# SCH_Blinking-Maple-PCB_2025-10-30.net
KiCad netlist of a schematic drawn in EasyEDA
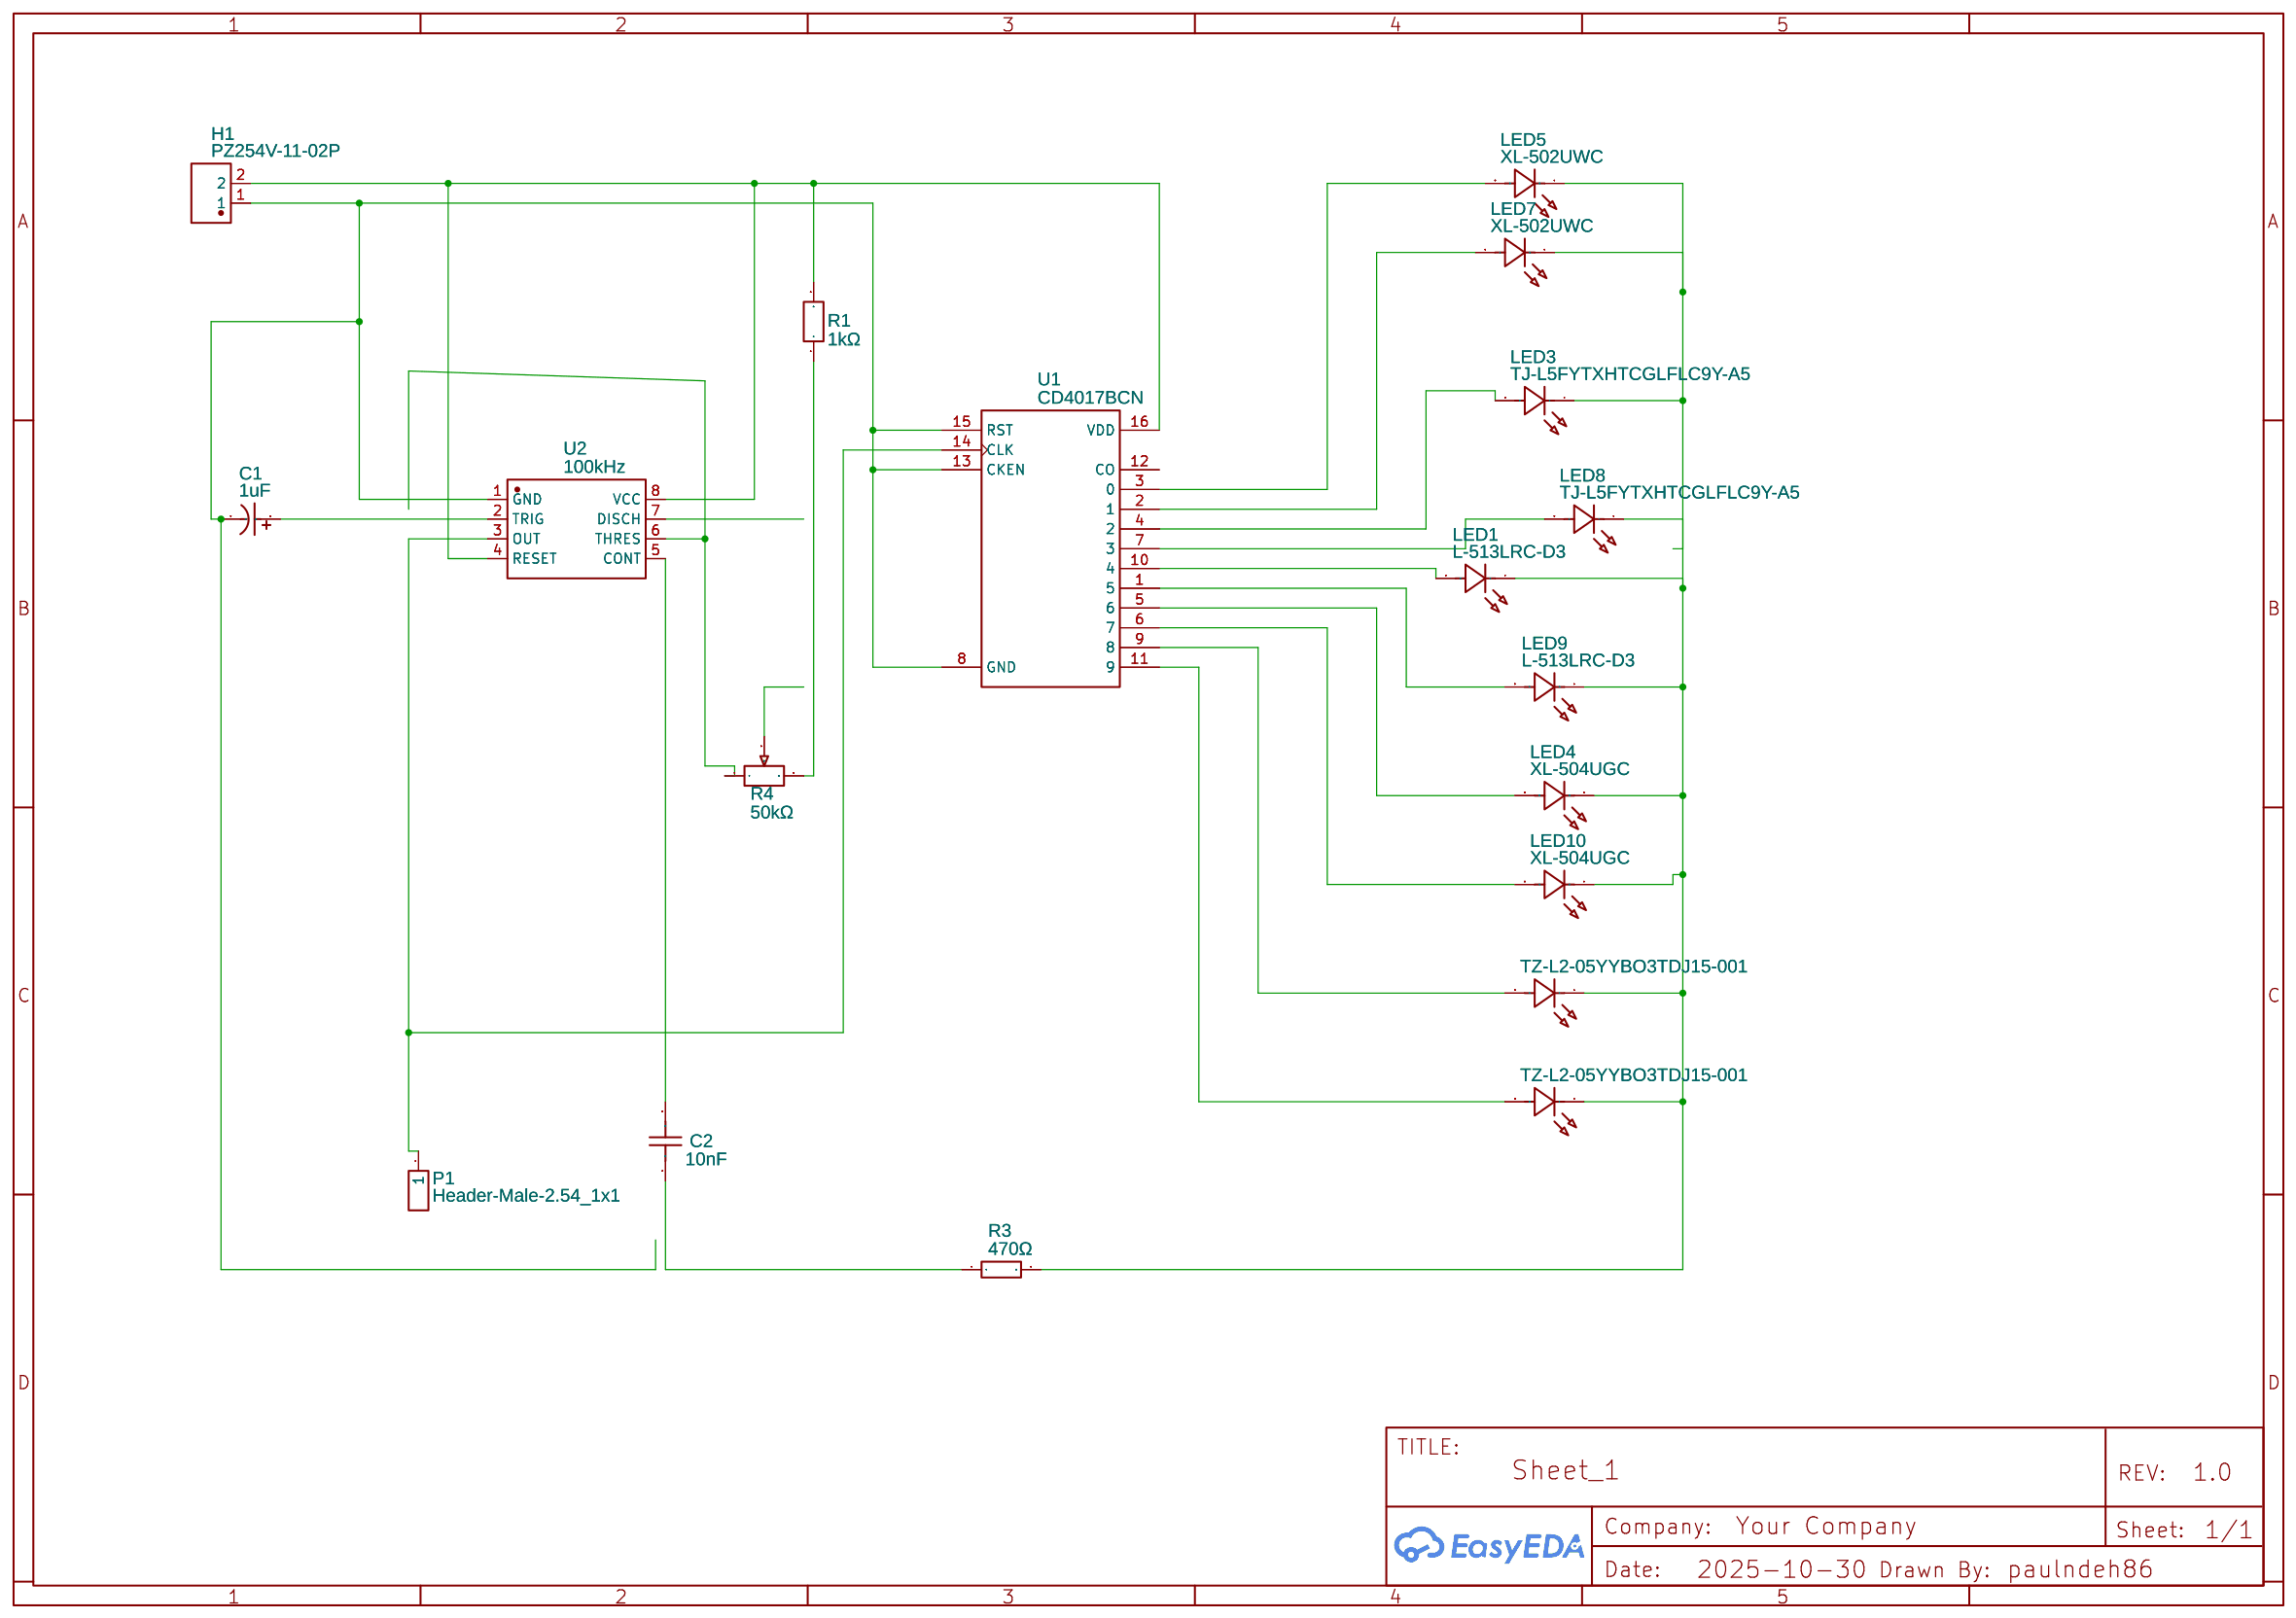
[diagram p0: schematic sheet]

(export (version "E")
  (design (tool "Eeschema 10.0.6"))
  (components
    (comp (ref "C1")
      (value "1uF")
      (fields (field (name "Manufacturer Part") "KF010M050C110A") (field (name "Manufacturer") "CapXon(丰宾)"))
      (libsource (lib "") (part "KF010M050C110A"))
    )
    (comp (ref "C2")
      (value "10nF")
      (fields (field (name "Manufacturer Part") "N09F1B103MN0B0S0N0") (field (name "Manufacturer") "STE(松田)"))
      (libsource (lib "") (part "N09F1B103MN0B0S0N0"))
    )
    (comp (ref "H1")
      (value "PZ254V-11-02P")
      (fields (field (name "Manufacturer") "XFCN(兴飞)"))
      (libsource (lib "") (part "PZ254V-11-02P"))
    )
    (comp (ref "LED1")
      (value "L-513LRC-D3")
      (fields (field (name "Manufacturer") "PARALIGHT(光鼎)"))
      (libsource (lib "") (part "L-513LRC-D3"))
    )
    (comp (ref "LED2")
      (value "TZ-L2-05YYBO3TDJ15-001")
      (fields (field (name "Manufacturer") "TUOZHAN(拓展光电)"))
      (libsource (lib "") (part "TZ-L2-05YYBO3TDJ15-001"))
    )
    (comp (ref "LED3")
      (value "TJ-L5FYTXHTCGLFLC9Y-A5")
      (fields (field (name "Manufacturer") "TOGIALED(统佳)"))
      (libsource (lib "") (part "TJ-L5FYTXHTCGLFLC9Y-A5"))
    )
    (comp (ref "LED4")
      (value "XL-504UGC")
      (fields (field (name "Manufacturer") "XINGLIGHT(成兴光)"))
      (libsource (lib "") (part "XL-504UGC"))
    )
    (comp (ref "LED5")
      (value "XL-502UWC")
      (fields (field (name "Manufacturer") "XINGLIGHT(成兴光)"))
      (libsource (lib "") (part "XL-502UWC"))
    )
    (comp (ref "LED7")
      (value "XL-502UWC")
      (fields (field (name "Manufacturer") "XINGLIGHT(成兴光)"))
      (libsource (lib "") (part "XL-502UWC"))
    )
    (comp (ref "LED8")
      (value "TJ-L5FYTXHTCGLFLC9Y-A5")
      (fields (field (name "Manufacturer") "TOGIALED(统佳)"))
      (libsource (lib "") (part "TJ-L5FYTXHTCGLFLC9Y-A5"))
    )
    (comp (ref "LED9")
      (value "L-513LRC-D3")
      (fields (field (name "Manufacturer") "PARALIGHT(光鼎)"))
      (libsource (lib "") (part "L-513LRC-D3"))
    )
    (comp (ref "LED10")
      (value "XL-504UGC")
      (fields (field (name "Manufacturer") "XINGLIGHT(成兴光)"))
      (libsource (lib "") (part "XL-504UGC"))
    )
    (comp (ref "LED11")
      (value "TZ-L2-05YYBO3TDJ15-001")
      (fields (field (name "Manufacturer") "TUOZHAN(拓展光电)"))
      (libsource (lib "") (part "TZ-L2-05YYBO3TDJ15-001"))
    )
    (comp (ref "P1")
      (value "Header-Male-2.54_1x1")
      (fields (field (name "Manufacturer Part") "2.54-1*1P针") (field (name "Manufacturer") "BOOMELE(博穆精密)"))
      (libsource (lib "") (part "Header-Male-2.54_1x1"))
    )
    (comp (ref "R1")
      (value "1kΩ")
      (fields (field (name "Manufacturer Part") "MF1/4W-1KΩ±1%T52") (field (name "Manufacturer") "华星机电"))
      (libsource (lib "") (part "MF1/4W-1KΩ±1%T52"))
    )
    (comp (ref "R3")
      (value "470Ω")
      (fields
        (field (name "Manufacturer Part") "MFR0W4F4700A50")
        (field (name "Manufacturer") "UNI-ROYAL(厚声)")
      )
      (libsource (lib "") (part "MFR0W4F4700A50"))
    )
    (comp (ref "R4")
      (value "50kΩ")
      (fields
        (field (name "Manufacturer Part") "ST-32EA 50K ohm (503)")
        (field (name "Manufacturer") "NIDEC(尼得科)")
      )
      (libsource (lib "") (part "ST-32EA 50K ohm (503)"))
    )
    (comp (ref "U1") (value "CD4017BCN") (libsource (lib "") (part "CD4017BCN")))
    (comp (ref "U2")
      (value "100kHz")
      (fields (field (name "Manufacturer Part") "NE555P") (field (name "Manufacturer") "TI(德州仪器)"))
      (libsource (lib "") (part "NE555P"))
    )
  )
  (nets
    (net (code "1") (name "Net-(C2-Pad1)") (class "Default")
      (node (ref "C2") (pin "1") (pinfunction "1_1") (pintype "unspecified"))
      (node (ref "R3") (pin "1") (pinfunction "1_1") (pintype "input"))
    )
    (net (code "2") (name "Net-(LED1-A)") (class "Default")
      (node (ref "LED1") (pin "2") (pinfunction "A_2") (pintype "unspecified"))
      (node (ref "U1") (pin "10") (pinfunction "4_10") (pintype "output"))
    )
    (net (code "3") (name "Net-(LED1-K)") (class "Default")
      (node (ref "LED1") (pin "1") (pinfunction "K_1") (pintype "unspecified"))
      (node (ref "LED10") (pin "1") (pinfunction "K_1") (pintype "unspecified"))
      (node (ref "LED11") (pin "1") (pinfunction "-_1") (pintype "unspecified"))
      (node (ref "LED2") (pin "1") (pinfunction "-_1") (pintype "unspecified"))
      (node (ref "LED4") (pin "1") (pinfunction "K_1") (pintype "unspecified"))
      (node (ref "LED8") (pin "1") (pinfunction "-_1") (pintype "unspecified"))
      (node (ref "LED9") (pin "1") (pinfunction "K_1") (pintype "unspecified"))
      (node (ref "R3") (pin "2") (pinfunction "2_2") (pintype "input"))
    )
    (net (code "4") (name "Net-(LED2-+)") (class "Default")
      (node (ref "LED2") (pin "2") (pinfunction "+_2") (pintype "unspecified"))
      (node (ref "U1") (pin "9") (pinfunction "8_9") (pintype "output"))
    )
    (net (code "5") (name "Net-(LED3-+)") (class "Default")
      (node (ref "LED3") (pin "2") (pinfunction "+_2") (pintype "unspecified"))
      (node (ref "U1") (pin "4") (pinfunction "2_4") (pintype "output"))
    )
    (net (code "6") (name "Net-(LED3--)") (class "Default")
      (node (ref "LED3") (pin "1") (pinfunction "-_1") (pintype "unspecified"))
      (node (ref "LED5") (pin "1") (pinfunction "K_1") (pintype "unspecified"))
      (node (ref "LED7") (pin "1") (pinfunction "K_1") (pintype "unspecified"))
    )
    (net (code "7") (name "Net-(LED4-A)") (class "Default")
      (node (ref "LED4") (pin "2") (pinfunction "A_2") (pintype "unspecified"))
      (node (ref "U1") (pin "5") (pinfunction "6_5") (pintype "output"))
    )
    (net (code "8") (name "Net-(LED5-A)") (class "Default")
      (node (ref "LED5") (pin "2") (pinfunction "A_2") (pintype "unspecified"))
      (node (ref "U1") (pin "3") (pinfunction "0_3") (pintype "output"))
    )
    (net (code "9") (name "Net-(LED7-A)") (class "Default")
      (node (ref "LED7") (pin "2") (pinfunction "A_2") (pintype "unspecified"))
      (node (ref "U1") (pin "2") (pinfunction "1_2") (pintype "output"))
    )
    (net (code "10") (name "Net-(LED8-+)") (class "Default")
      (node (ref "LED8") (pin "2") (pinfunction "+_2") (pintype "unspecified"))
      (node (ref "U1") (pin "7") (pinfunction "3_7") (pintype "output"))
    )
    (net (code "11") (name "Net-(LED9-A)") (class "Default")
      (node (ref "LED9") (pin "2") (pinfunction "A_2") (pintype "unspecified"))
      (node (ref "U1") (pin "1") (pinfunction "5_1") (pintype "output"))
    )
    (net (code "12") (name "Net-(LED10-A)") (class "Default")
      (node (ref "LED10") (pin "2") (pinfunction "A_2") (pintype "unspecified"))
      (node (ref "U1") (pin "6") (pinfunction "7_6") (pintype "output"))
    )
    (net (code "13") (name "Net-(LED11-+)") (class "Default")
      (node (ref "LED11") (pin "2") (pinfunction "+_2") (pintype "unspecified"))
      (node (ref "U1") (pin "11") (pinfunction "9_11") (pintype "output"))
    )
    (net (code "14") (name "Net-(R1-Pad1)") (class "Default")
      (node (ref "R1") (pin "1") (pinfunction "1_1") (pintype "unspecified"))
      (node (ref "R4") (pin "3") (pinfunction "3_3") (pintype "input"))
    )
    (net (code "15") (name "Net-(U1-CKEN)") (class "Default")
      (node (ref "C1") (pin "2") (pinfunction "2_2") (pintype "input"))
      (node (ref "H1") (pin "1") (pinfunction "1_1") (pintype "unspecified"))
      (node (ref "U1") (pin "13") (pinfunction "CKEN_13") (pintype "unspecified"))
      (node (ref "U1") (pin "15") (pinfunction "RST_15") (pintype "unspecified"))
      (node (ref "U1") (pin "8") (pinfunction "GND_8") (pintype "passive"))
      (node (ref "U2") (pin "1") (pinfunction "GND_1") (pintype "unspecified"))
    )
    (net (code "16") (name "Net-(U1-CLK)") (class "Default")
      (node (ref "P1") (pin "1") (pinfunction "1_1") (pintype "input"))
      (node (ref "U1") (pin "14") (pinfunction "CLK_14") (pintype "unspecified"))
      (node (ref "U2") (pin "3") (pinfunction "OUT_3") (pintype "unspecified"))
    )
    (net (code "17") (name "Net-(U1-VDD)") (class "Default")
      (node (ref "H1") (pin "2") (pinfunction "2_2") (pintype "unspecified"))
      (node (ref "R1") (pin "2") (pinfunction "2_2") (pintype "unspecified"))
      (node (ref "U1") (pin "16") (pinfunction "VDD_16") (pintype "passive"))
      (node (ref "U2") (pin "4") (pinfunction "RESET_4") (pintype "unspecified"))
      (node (ref "U2") (pin "8") (pinfunction "VCC_8") (pintype "unspecified"))
    )
    (net (code "18") (name "Net-(U2-CONT)") (class "Default")
      (node (ref "C2") (pin "2") (pinfunction "2_2") (pintype "unspecified"))
      (node (ref "U2") (pin "5") (pinfunction "CONT_5") (pintype "unspecified"))
    )
    (net (code "19") (name "Net-(U2-THRES)") (class "Default")
      (node (ref "R4") (pin "1") (pinfunction "1_1") (pintype "input"))
      (node (ref "U2") (pin "6") (pinfunction "THRES_6") (pintype "unspecified"))
    )
    (net (code "20") (name "Net-(U2-TRIG)") (class "Default")
      (node (ref "C1") (pin "1") (pinfunction "1_1") (pintype "input"))
      (node (ref "U2") (pin "2") (pinfunction "TRIG_2") (pintype "unspecified"))
    )
    (net (code "21") (name "unconnected-(R4-Pad2)") (class "Default")
      (node (ref "R4") (pin "2") (pinfunction "2_2") (pintype "input"))
    )
    (net (code "22") (name "unconnected-(U1-CO-Pad12)") (class "Default")
      (node (ref "U1") (pin "12") (pinfunction "CO_12") (pintype "output"))
    )
    (net (code "23") (name "unconnected-(U2-DISCH-Pad7)") (class "Default")
      (node (ref "U2") (pin "7") (pinfunction "DISCH_7") (pintype "unspecified"))
    )
  )
)
